# Signal_TX.net
KiCad netlist of a schematic drawn in Altium Designer
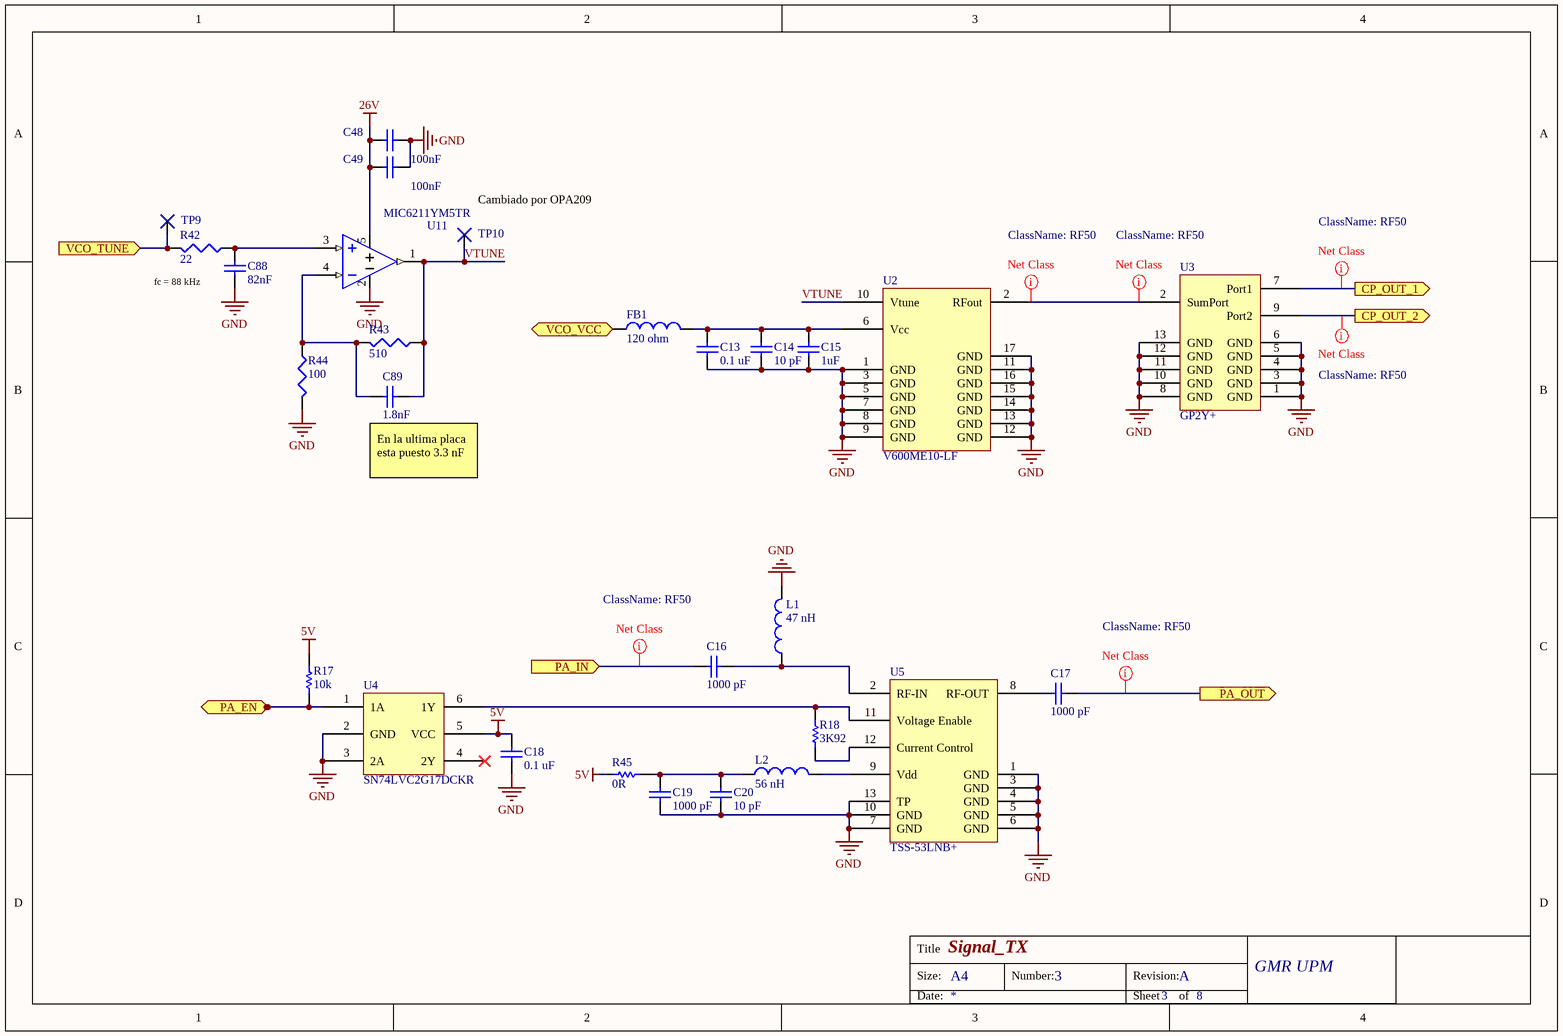
[diagram p0: Signal_TX.SchDoc]

(export (version "E")
  (design (tool "Eeschema 10.0.6"))
  (components
    (comp (ref "C13")
      (value "0.1 uF")
      (footprint "0603 Cap")
      (description "CAP CER 0.1UF 16V X7R 0603")
      (fields
        (field (name "MANUFACTURER") "Yageo")
        (field (name "MANUFACTURER PART NUMBER") "CC0603KRX7R7BB104")
      )
      (libsource (lib "Componentes_base") (part "CC0603KRX7R7BB104"))
    )
    (comp (ref "C14")
      (value "10 pF")
      (footprint "CAPC1005X05L")
      (description "CAP CER 10PF 50V 5% NP0 0402")
      (fields
        (field (name "MANUFACTURER") "Samsung Electro-Mechanics America, Inc")
        (field (name "MANUFACTURER PART NUMBER") "CL05C100JB5NNNC")
      )
      (libsource (lib "Componentes_base") (part "CL05C100JB5NNNC"))
    )
    (comp (ref "C15")
      (value "1uF")
      (footprint "0603 Cap")
      (description "CAP CER 1UF 16V X7R 0603")
      (fields
        (field (name "MANUFACTURER") "Samsung Electro-Mechanics America, Inc.")
        (field (name "MANUFACTURER PART NUMBER") "CL10B105MO8NNWC")
      )
      (libsource (lib "Componentes_base") (part "CL10B105MO8NNWC"))
    )
    (comp (ref "C16")
      (value "1000 pF")
      (footprint "CAPC1005X05L")
      (description "CAP CER 1000PF 25V 5% NP0 0402")
      (fields
        (field (name "MANUFACTURER") "Samsung Electro-Mechanics America, Inc")
        (field (name "MANUFACTURER PART NUMBER") "CL05C102JB5NNNC")
      )
      (libsource (lib "Componentes_base") (part "CL05C102JA5NNNC"))
    )
    (comp (ref "C17")
      (value "1000 pF")
      (footprint "CAPC1005X05L")
      (description "CAP CER 1000PF 25V 5% NP0 0402")
      (fields
        (field (name "MANUFACTURER") "Samsung Electro-Mechanics America, Inc")
        (field (name "MANUFACTURER PART NUMBER") "CL05C102JB5NNNC")
      )
      (libsource (lib "Componentes_base") (part "CL05C102JA5NNNC"))
    )
    (comp (ref "C18")
      (value "0.1 uF")
      (footprint "0603 Cap")
      (description "CAP CER 0.1UF 16V X7R 0603")
      (fields
        (field (name "MANUFACTURER") "Yageo")
        (field (name "MANUFACTURER PART NUMBER") "CC0603KRX7R7BB104")
      )
      (libsource (lib "Componentes_base") (part "CC0603KRX7R7BB104"))
    )
    (comp (ref "C19")
      (value "1000 pF")
      (footprint "CAPC1005X05L")
      (description "CAP CER 1000PF 25V 5% NP0 0402")
      (fields
        (field (name "MANUFACTURER") "Samsung Electro-Mechanics America, Inc")
        (field (name "MANUFACTURER PART NUMBER") "CL05C102JB5NNNC")
      )
      (libsource (lib "Componentes_base") (part "CL05C102JA5NNNC"))
    )
    (comp (ref "C20")
      (value "10 pF")
      (footprint "CAPC1005X05L")
      (description "CAP CER 10PF 50V 5% NP0 0402")
      (fields
        (field (name "MANUFACTURER") "Samsung Electro-Mechanics America, Inc")
        (field (name "MANUFACTURER PART NUMBER") "CL05C100JB5NNNC")
      )
      (libsource (lib "Componentes_base") (part "CL05C100JB5NNNC"))
    )
    (comp (ref "C48")
      (value "100nF")
      (footprint "0603 Cap")
      (description "CAP CER 0.1UF 16V X7R 0603")
      (fields
        (field (name "MANUFACTURER") "KEMET")
        (field (name "MANUFACTURER PART NUMBER") "C0603C104K4RACTU")
      )
      (libsource (lib "Componentes_base") (part "C0603C104K4RACTU"))
    )
    (comp (ref "C49")
      (value "100nF")
      (footprint "0603 Cap")
      (description "CAP CER 0.1UF 16V X7R 0603")
      (fields
        (field (name "MANUFACTURER") "KEMET")
        (field (name "MANUFACTURER PART NUMBER") "C0603C104K4RACTU")
      )
      (libsource (lib "Componentes_base") (part "C0603C104K4RACTU"))
    )
    (comp (ref "C88")
      (value "82nF")
      (footprint "0603 Cap")
      (description "CAP CER 0.1UF 16V X7R 0603")
      (fields
        (field (name "MANUFACTURER") "KEMET")
        (field (name "MANUFACTURER PART NUMBER") "C0603C104K4RACTU")
      )
      (libsource (lib "Componentes_base") (part "C0603C104K4RACTU"))
    )
    (comp (ref "C89")
      (value "1.8nF")
      (footprint "0603 Cap")
      (description "CAP CER 0.1UF 16V X7R 0603")
      (fields
        (field (name "MANUFACTURER") "KEMET")
        (field (name "MANUFACTURER PART NUMBER") "C0603C104K4RACTU")
      )
      (libsource (lib "Componentes_base") (part "C0603C104K4RACTU"))
    )
    (comp (ref "FB1")
      (value "120 ohm")
      (footprint "INDC1608X08L")
      (description "FERRITE BEAD 120 OHM 0603 1LN")
      (fields
        (field (name "MANUFACTURER") "Murata Electronics North America")
        (field (name "MANUFACTURER PART NUMBER") "BLM18PG121SN1D")
      )
      (libsource (lib "Componentes_base") (part "BLM18PG121SN1D"))
    )
    (comp (ref "L1")
      (value "47 nH")
      (footprint "INDC1005X07L")
      (description "COILCRAFT - 0402CS-47NXGLU - INDUCTOR, RF, 47NH, 2%, 2.1GHZ, SMD")
      (fields
        (field (name "MANUFACTURER") "COILCRAFT")
        (field (name "MANUFACTURER PART NUMBER") "0402CS-47NXGLU")
      )
      (libsource (lib "Componentes_base") (part "0402CS-47NXGLU"))
    )
    (comp (ref "L2")
      (value "56 nH")
      (footprint "INDC1005X07L")
      (description "Fixed Inductors 0402CS HiFreq Chip 56 nH 5 % 0.1 A")
      (fields
        (field (name "MANUFACTURER") "Coilcraft")
        (field (name "MANUFACTURER PART NUMBER") "0402CS-56NXJLU")
      )
      (libsource (lib "Componentes_base") (part "0402CS-56NXJLU"))
    )
    (comp (ref "R17")
      (value "10k")
      (footprint "0603 Res")
      (description "SMD Resistor, 1%, 0.1W, 0603")
      (fields (field (name "TOLERANCE") "1"))
      (libsource (lib "Componentes_base") (part "R_0603"))
    )
    (comp (ref "R18")
      (value "3K92")
      (footprint "0603 Res")
      (description "SMD Resistor, 1%, 0.1W, 0603")
      (fields (field (name "TOLERANCE") "1"))
      (libsource (lib "Componentes_base") (part "R_0603"))
    )
    (comp (ref "R42")
      (value "22")
      (footprint "J1-0603")
      (description "Resistor")
      (fields (field (name "PUBLISHER") "Altium Limited"))
      (libsource (lib "Miscellaneous Devices") (part "Res3"))
    )
    (comp (ref "R43")
      (value "510")
      (footprint "J1-0603")
      (description "Resistor")
      (fields (field (name "PUBLISHER") "Altium Limited"))
      (libsource (lib "Miscellaneous Devices") (part "Res3"))
    )
    (comp (ref "R44")
      (value "100")
      (footprint "J1-0603")
      (description "Resistor")
      (fields (field (name "PUBLISHER") "Altium Limited"))
      (libsource (lib "Miscellaneous Devices") (part "Res3"))
    )
    (comp (ref "R45")
      (value "0R")
      (footprint "0603 Res")
      (description "SMD Resistor, 1%, 0.1W, 0603")
      (fields (field (name "TOLERANCE") "1"))
      (libsource (lib "Componentes_base") (part "R_0603"))
    )
    (comp (ref "TP9")
      (value "TEST_POINT_PIN")
      (footprint "TESTPOINT")
      (description "Test point for single pin")
      (libsource (lib "Componentes_base") (part "TEST_POINT_PIN"))
    )
    (comp (ref "TP10")
      (value "TEST_POINT_PIN")
      (footprint "TESTPOINT")
      (description "Test point for single pin")
      (libsource (lib "Componentes_base") (part "TEST_POINT_PIN"))
    )
    (comp (ref "U2")
      (value "V600ME10-LF")
      (footprint "CK605")
      (description "Voltage-Controlled Oscillator SMD")
      (fields (field (name "MANUFACTURER") "ZCOMM"))
      (libsource (lib "Schlib1") (part "V600ME10-LF"))
    )
    (comp (ref "U3")
      (value "GP2Y+")
      (footprint "DQ1225")
      (description "Power Splitter/Combiner")
      (fields (field (name "MANUFACTURER") "Minicircuits"))
      (libsource (lib "Schlib1") (part "GP2Y+"))
    )
    (comp (ref "U4")
      (value "SN74LVC2G17DCKR")
      (footprint "DCK (R-PDSO-G6)")
      (description "IC BUF NON-INVERT 5.5V SC70-6")
      (fields (field (name "MANUFACTURER") "Texas Instruments") (field (name "BASE PART NUMBER") "74LVC2G17"))
      (libsource (lib "Schlib1") (part "SN74LVC2G17DCKR"))
    )
    (comp (ref "U5")
      (value "TSS-53LNB+")
      (footprint "DQ1225")
      (description "Low Noise Bypass Amplier")
      (fields (field (name "MANUFACTURER") "Minicircuits"))
      (libsource (lib "Schlib1") (part "TSS-53LNB+"))
    )
    (comp (ref "U11")
      (value "MIC6211YM5TR")
      (footprint "SOT95P280X90-5N2")
      (description "IC OPAMP GP 2.5MHZ SOT23-5")
      (fields (field (name "MANUFACTURER") "Microchip Micrel"))
      (libsource (lib "Schlib1") (part "MIC6211YM5TR"))
    )
  )
  (nets
    (net (code "1") (name "/CP_OUT_1") (class "Default")
      (node (ref "U3") (pin "7") (pinfunction "Port1_7") (pintype "passive"))
    )
    (net (code "2") (name "/CP_OUT_2") (class "Default")
      (node (ref "U3") (pin "9") (pinfunction "Port2_9") (pintype "passive"))
    )
    (net (code "3") (name "/PA_EN") (class "Default")
      (node (ref "R17") (pin "1") (pinfunction "1_1") (pintype "passive"))
      (node (ref "U4") (pin "1") (pinfunction "1A_1") (pintype "passive"))
    )
    (net (code "4") (name "/PA_IN") (class "Default")
      (node (ref "C16") (pin "1") (pinfunction "1_1") (pintype "passive"))
    )
    (net (code "5") (name "/PA_OUT") (class "Default")
      (node (ref "C17") (pin "1") (pinfunction "1_1") (pintype "passive"))
    )
    (net (code "6") (name "/VCO_TUNE") (class "Default")
      (node (ref "R42") (pin "2") (pinfunction "2_2") (pintype "passive"))
      (node (ref "TP9") (pin "1") (pinfunction "1_1") (pintype "passive"))
    )
    (net (code "7") (name "/VCO_VCC") (class "Default")
      (node (ref "FB1") (pin "2") (pinfunction "2_2") (pintype "passive"))
    )
    (net (code "8") (name "/VTUNE") (class "Default")
      (node (ref "C89") (pin "1") (pinfunction "1_1") (pintype "passive"))
      (node (ref "R43") (pin "1") (pinfunction "1_1") (pintype "passive"))
      (node (ref "TP10") (pin "1") (pinfunction "1_1") (pintype "passive"))
      (node (ref "U11") (pin "1") (pinfunction "OUTA_1") (pintype "output"))
      (node (ref "U2") (pin "10") (pinfunction "Vtune_10") (pintype "passive"))
    )
    (net (code "9") (name "5V") (class "Default")
      (node (ref "C18") (pin "2") (pinfunction "2_2") (pintype "passive"))
      (node (ref "R17") (pin "2") (pinfunction "2_2") (pintype "passive"))
      (node (ref "R45") (pin "2") (pinfunction "2_2") (pintype "passive"))
      (node (ref "U4") (pin "5") (pinfunction "VCC_5") (pintype "passive"))
    )
    (net (code "10") (name "26V") (class "Default")
      (node (ref "C48") (pin "2") (pinfunction "2_2") (pintype "passive"))
      (node (ref "C49") (pin "2") (pinfunction "2_2") (pintype "passive"))
      (node (ref "U11") (pin "5") (pinfunction "V+_5") (pintype "power_in"))
    )
    (net (code "11") (name "GND") (class "Default")
      (node (ref "C13") (pin "1") (pinfunction "1_1") (pintype "passive"))
      (node (ref "C14") (pin "1") (pinfunction "1_1") (pintype "passive"))
      (node (ref "C15") (pin "1") (pinfunction "1_1") (pintype "passive"))
      (node (ref "C18") (pin "1") (pinfunction "1_1") (pintype "passive"))
      (node (ref "C19") (pin "1") (pinfunction "1_1") (pintype "passive"))
      (node (ref "C20") (pin "1") (pinfunction "1_1") (pintype "passive"))
      (node (ref "C48") (pin "1") (pinfunction "1_1") (pintype "passive"))
      (node (ref "C49") (pin "1") (pinfunction "1_1") (pintype "passive"))
      (node (ref "C88") (pin "1") (pinfunction "1_1") (pintype "passive"))
      (node (ref "L1") (pin "2") (pinfunction "2_2") (pintype "passive"))
      (node (ref "R44") (pin "2") (pinfunction "2_2") (pintype "passive"))
      (node (ref "U11") (pin "2") (pinfunction "V-_2") (pintype "power_in"))
      (node (ref "U2") (pin "1") (pinfunction "GND_1") (pintype "power_in"))
      (node (ref "U2") (pin "11") (pinfunction "GND_11") (pintype "power_in"))
      (node (ref "U2") (pin "12") (pinfunction "GND_12") (pintype "power_in"))
      (node (ref "U2") (pin "13") (pinfunction "GND_13") (pintype "power_in"))
      (node (ref "U2") (pin "14") (pinfunction "GND_14") (pintype "power_in"))
      (node (ref "U2") (pin "15") (pinfunction "GND_15") (pintype "power_in"))
      (node (ref "U2") (pin "16") (pinfunction "GND_16") (pintype "power_in"))
      (node (ref "U2") (pin "17") (pinfunction "GND_17") (pintype "power_in"))
      (node (ref "U2") (pin "3") (pinfunction "GND_3") (pintype "power_in"))
      (node (ref "U2") (pin "5") (pinfunction "GND_5") (pintype "power_in"))
      (node (ref "U2") (pin "7") (pinfunction "GND_7") (pintype "power_in"))
      (node (ref "U2") (pin "8") (pinfunction "GND_8") (pintype "power_in"))
      (node (ref "U2") (pin "9") (pinfunction "GND_9") (pintype "power_in"))
      (node (ref "U3") (pin "1") (pinfunction "GND_1") (pintype "power_in"))
      (node (ref "U3") (pin "10") (pinfunction "GND_10") (pintype "power_in"))
      (node (ref "U3") (pin "11") (pinfunction "GND_11") (pintype "power_in"))
      (node (ref "U3") (pin "12") (pinfunction "GND_12") (pintype "power_in"))
      (node (ref "U3") (pin "13") (pinfunction "GND_13") (pintype "power_in"))
      (node (ref "U3") (pin "3") (pinfunction "GND_3") (pintype "power_in"))
      (node (ref "U3") (pin "4") (pinfunction "GND_4") (pintype "power_in"))
      (node (ref "U3") (pin "5") (pinfunction "GND_5") (pintype "power_in"))
      (node (ref "U3") (pin "6") (pinfunction "GND_6") (pintype "power_in"))
      (node (ref "U3") (pin "8") (pinfunction "GND_8") (pintype "power_in"))
      (node (ref "U4") (pin "2") (pinfunction "GND_2") (pintype "passive"))
      (node (ref "U4") (pin "3") (pinfunction "2A_3") (pintype "power_in"))
      (node (ref "U5") (pin "1") (pinfunction "GND_1") (pintype "power_in"))
      (node (ref "U5") (pin "10") (pinfunction "GND_10") (pintype "power_in"))
      (node (ref "U5") (pin "13") (pinfunction "TP_13") (pintype "power_in"))
      (node (ref "U5") (pin "3") (pinfunction "GND_3") (pintype "power_in"))
      (node (ref "U5") (pin "4") (pinfunction "GND_4") (pintype "power_in"))
      (node (ref "U5") (pin "5") (pinfunction "GND_5") (pintype "power_in"))
      (node (ref "U5") (pin "6") (pinfunction "GND_6") (pintype "power_in"))
      (node (ref "U5") (pin "7") (pinfunction "GND_7") (pintype "power_in"))
    )
    (net (code "12") (name "Net-(C19-Pad2)") (class "Default")
      (node (ref "C19") (pin "2") (pinfunction "2_2") (pintype "passive"))
      (node (ref "C20") (pin "2") (pinfunction "2_2") (pintype "passive"))
      (node (ref "L2") (pin "1") (pinfunction "1_1") (pintype "passive"))
      (node (ref "R45") (pin "1") (pinfunction "1_1") (pintype "passive"))
    )
    (net (code "13") (name "Net-(U2-RFout)") (class "Default")
      (node (ref "U2") (pin "2") (pinfunction "RFout_2") (pintype "passive"))
      (node (ref "U3") (pin "2") (pinfunction "SumPort_2") (pintype "passive"))
    )
    (net (code "14") (name "Net-(U2-Vcc)") (class "Default")
      (node (ref "C13") (pin "2") (pinfunction "2_2") (pintype "passive"))
      (node (ref "C14") (pin "2") (pinfunction "2_2") (pintype "passive"))
      (node (ref "C15") (pin "2") (pinfunction "2_2") (pintype "passive"))
      (node (ref "FB1") (pin "1") (pinfunction "1_1") (pintype "passive"))
      (node (ref "U2") (pin "6") (pinfunction "Vcc_6") (pintype "power_in"))
    )
    (net (code "15") (name "Net-(U4-1Y)") (class "Default")
      (node (ref "R18") (pin "2") (pinfunction "2_2") (pintype "passive"))
      (node (ref "U4") (pin "6") (pinfunction "1Y_6") (pintype "passive"))
      (node (ref "U5") (pin "11") (pinfunction "Voltage_Enable_11") (pintype "passive"))
    )
    (net (code "16") (name "Net-(U5-Current_Control)") (class "Default")
      (node (ref "R18") (pin "1") (pinfunction "1_1") (pintype "passive"))
      (node (ref "U5") (pin "12") (pinfunction "Current_Control_12") (pintype "passive"))
    )
    (net (code "17") (name "Net-(U5-RF-IN)") (class "Default")
      (node (ref "C16") (pin "2") (pinfunction "2_2") (pintype "passive"))
      (node (ref "L1") (pin "1") (pinfunction "1_1") (pintype "passive"))
      (node (ref "U5") (pin "2") (pinfunction "RF-IN_2") (pintype "passive"))
    )
    (net (code "18") (name "Net-(U5-RF-OUT)") (class "Default")
      (node (ref "C17") (pin "2") (pinfunction "2_2") (pintype "passive"))
      (node (ref "U5") (pin "8") (pinfunction "RF-OUT_8") (pintype "passive"))
    )
    (net (code "19") (name "Net-(U5-Vdd)") (class "Default")
      (node (ref "L2") (pin "2") (pinfunction "2_2") (pintype "passive"))
      (node (ref "U5") (pin "9") (pinfunction "Vdd_9") (pintype "power_in"))
    )
    (net (code "20") (name "Net-(U11-IN+)") (class "Default")
      (node (ref "C88") (pin "2") (pinfunction "2_2") (pintype "passive"))
      (node (ref "R42") (pin "1") (pinfunction "1_1") (pintype "passive"))
      (node (ref "U11") (pin "3") (pinfunction "IN+_3") (pintype "input"))
    )
    (net (code "21") (name "Net-(U11-IN-)") (class "Default")
      (node (ref "C89") (pin "2") (pinfunction "2_2") (pintype "passive"))
      (node (ref "R43") (pin "2") (pinfunction "2_2") (pintype "passive"))
      (node (ref "R44") (pin "1") (pinfunction "1_1") (pintype "passive"))
      (node (ref "U11") (pin "4") (pinfunction "IN-_4") (pintype "input"))
    )
    (net (code "22") (name "unconnected-(U4-2Y-Pad4)") (class "Default")
      (node (ref "U4") (pin "4") (pinfunction "2Y_4") (pintype "power_in+no_connect"))
    )
  )
)
